# btkb.net
KiCad netlist of a schematic drawn in EAGLE
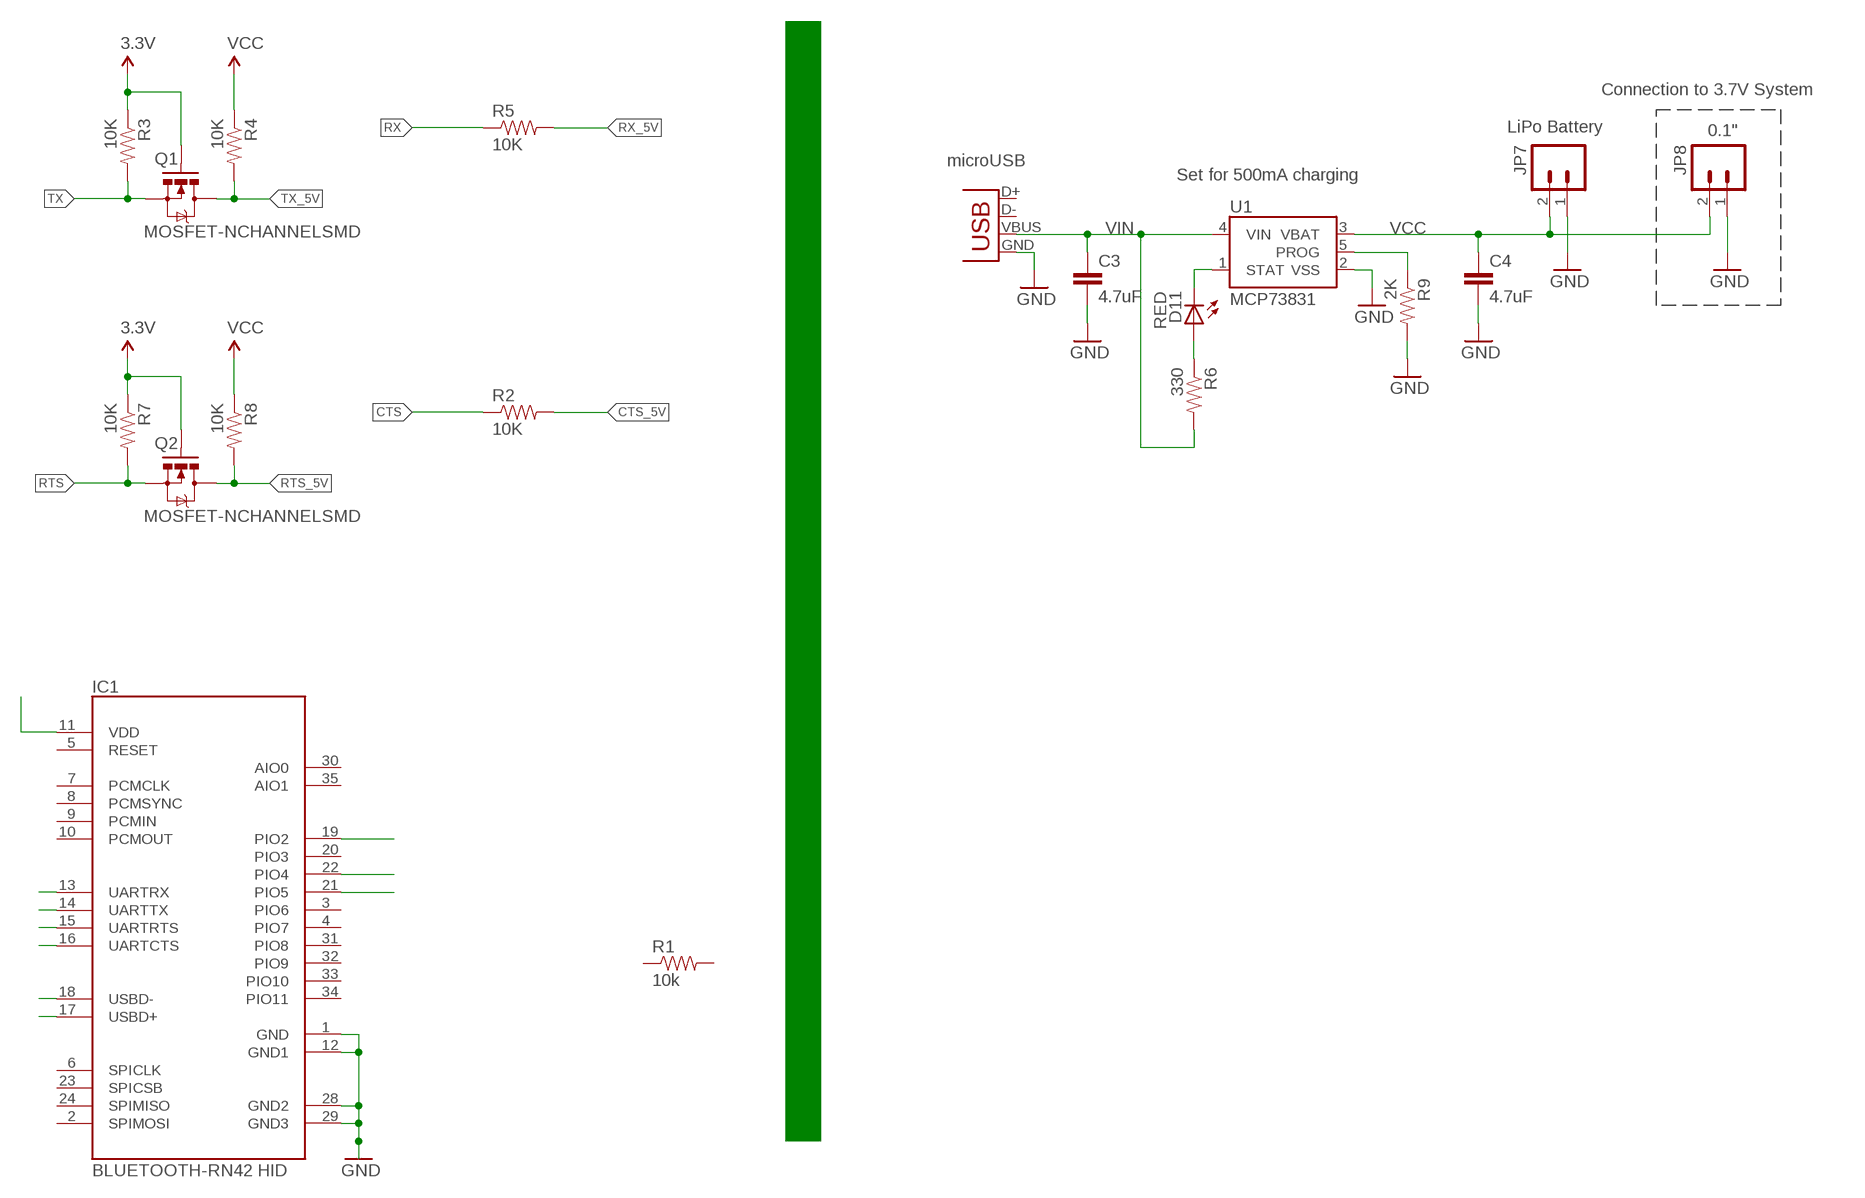
[diagram p0: schematic, sheet 1]

(export (version "E")
  (design (tool "Eeschema 10.0.6"))
  (components
    (comp (ref "C3")
      (value "4.7uF")
      (footprint "eagle-import:0402-CAP")
      (libsource (lib "eagle-import") (part "CAP0402-CAP"))
    )
    (comp (ref "C4")
      (value "4.7uF")
      (footprint "eagle-import:0402-CAP")
      (libsource (lib "eagle-import") (part "CAP0402-CAP"))
    )
    (comp (ref "D11")
      (value "RED")
      (footprint "eagle-import:LED-0603")
      (libsource (lib "eagle-import") (part "LED0603"))
    )
    (comp (ref "IC1")
      (value "BLUETOOTH-RN42 HID")
      (footprint "eagle-import:RN41")
      (libsource (lib "eagle-import") (part "BLUETOOTH-RN41{dblquote}"))
    )
    (comp (ref "JP7")
      (value "LiPo Battery")
      (footprint "eagle-import:JST-2-SMD")
      (libsource (lib "eagle-import") (part "M02-JST-2MM-SMT"))
    )
    (comp (ref "JP8")
      (value "M02PTH")
      (footprint "eagle-import:1X02")
      (libsource (lib "eagle-import") (part "M02PTH"))
    )
    (comp (ref "Q1")
      (value "MOSFET-NCHANNELSMD")
      (footprint "eagle-import:SOT23-3")
      (libsource (lib "eagle-import") (part "MOSFET-NCHANNELSMD"))
    )
    (comp (ref "Q2")
      (value "MOSFET-NCHANNELSMD")
      (footprint "eagle-import:SOT23-3")
      (libsource (lib "eagle-import") (part "MOSFET-NCHANNELSMD"))
    )
    (comp (ref "R1")
      (value "10k")
      (footprint "eagle-import:0805")
      (libsource (lib "eagle-import") (part "0.22OHM-1/4W-1%(0805)"))
    )
    (comp (ref "R2")
      (value "10K")
      (footprint "eagle-import:0603-RES")
      (libsource (lib "eagle-import") (part "RESISTOR0603-RES"))
    )
    (comp (ref "R3")
      (value "10K")
      (footprint "eagle-import:0603-RES")
      (libsource (lib "eagle-import") (part "RESISTOR0603-RES"))
    )
    (comp (ref "R4")
      (value "10K")
      (footprint "eagle-import:0603-RES")
      (libsource (lib "eagle-import") (part "RESISTOR0603-RES"))
    )
    (comp (ref "R5")
      (value "10K")
      (footprint "eagle-import:0603-RES")
      (libsource (lib "eagle-import") (part "RESISTOR0603-RES"))
    )
    (comp (ref "R6")
      (value "330")
      (footprint "eagle-import:0402-RES")
      (libsource (lib "eagle-import") (part "RESISTOR0402-RES"))
    )
    (comp (ref "R7")
      (value "10K")
      (footprint "eagle-import:0603-RES")
      (libsource (lib "eagle-import") (part "RESISTOR0603-RES"))
    )
    (comp (ref "R8")
      (value "10K")
      (footprint "eagle-import:0603-RES")
      (libsource (lib "eagle-import") (part "RESISTOR0603-RES"))
    )
    (comp (ref "R9")
      (value "2K")
      (footprint "eagle-import:0402-RES")
      (libsource (lib "eagle-import") (part "RESISTOR0402-RES"))
    )
    (comp (ref "U1")
      (value "MCP73831")
      (footprint "eagle-import:SOT23-5")
      (libsource (lib "eagle-import") (part "MCP73831"))
    )
    (comp (ref "X1")
      (value "Micro USB")
      (footprint "eagle-import:USB-MICROB")
      (libsource (lib "eagle-import") (part "USB-MICROB"))
    )
  )
  (nets
    (net (code "1") (name "/VIN") (class "Default")
      (node (ref "C3") (pin "1") (pinfunction "1_1") (pintype "passive"))
      (node (ref "R6") (pin "2") (pinfunction "2_2") (pintype "passive"))
      (node (ref "U1") (pin "4") (pinfunction "VIN_4") (pintype "power_in"))
      (node (ref "X1") (pin "VBUS") (pinfunction "VBUS_VBUS") (pintype "bidirectional"))
    )
    (net (code "2") (name "3.3V") (class "Default")
      (node (ref "Q1") (pin "1") (pinfunction "G_1") (pintype "passive"))
      (node (ref "Q2") (pin "1") (pinfunction "G_1") (pintype "passive"))
      (node (ref "R3") (pin "1") (pinfunction "1_1") (pintype "passive"))
      (node (ref "R7") (pin "1") (pinfunction "1_1") (pintype "passive"))
    )
    (net (code "3") (name "CTS") (class "Default")
      (node (ref "R2") (pin "1") (pinfunction "1_1") (pintype "passive"))
    )
    (net (code "4") (name "CTS_5V") (class "Default")
      (node (ref "R2") (pin "2") (pinfunction "2_2") (pintype "passive"))
    )
    (net (code "5") (name "GND") (class "Default")
      (node (ref "C3") (pin "2") (pinfunction "2_2") (pintype "passive"))
      (node (ref "C4") (pin "2") (pinfunction "2_2") (pintype "passive"))
      (node (ref "IC1") (pin "1") (pinfunction "GND_1") (pintype "bidirectional"))
      (node (ref "IC1") (pin "12") (pinfunction "GND1_12") (pintype "bidirectional"))
      (node (ref "IC1") (pin "28") (pinfunction "GND2_28") (pintype "bidirectional"))
      (node (ref "IC1") (pin "29") (pinfunction "GND3_29") (pintype "bidirectional"))
      (node (ref "JP7") (pin "1") (pinfunction "1_1") (pintype "passive"))
      (node (ref "JP8") (pin "1") (pinfunction "1_1") (pintype "passive"))
      (node (ref "R9") (pin "2") (pinfunction "2_2") (pintype "passive"))
      (node (ref "U1") (pin "2") (pinfunction "VSS_2") (pintype "power_in"))
      (node (ref "X1") (pin "GND") (pinfunction "GND_GND") (pintype "bidirectional"))
    )
    (net (code "6") (name "Net-(D11-PadA)") (class "Default")
      (node (ref "D11") (pin "A") (pinfunction "A_A") (pintype "passive"))
      (node (ref "R6") (pin "1") (pinfunction "1_1") (pintype "passive"))
    )
    (net (code "7") (name "Net-(U1-PROG)") (class "Default")
      (node (ref "R9") (pin "1") (pinfunction "1_1") (pintype "passive"))
      (node (ref "U1") (pin "5") (pinfunction "PROG_5") (pintype "input"))
    )
    (net (code "8") (name "Net-(U1-STAT)") (class "Default")
      (node (ref "D11") (pin "C") (pinfunction "C_C") (pintype "passive"))
      (node (ref "U1") (pin "1") (pinfunction "STAT_1") (pintype "output"))
    )
    (net (code "9") (name "RTS") (class "Default")
      (node (ref "Q2") (pin "2") (pinfunction "S_2") (pintype "passive"))
      (node (ref "R7") (pin "2") (pinfunction "2_2") (pintype "passive"))
    )
    (net (code "10") (name "RTS_5V") (class "Default")
      (node (ref "Q2") (pin "3") (pinfunction "D_3") (pintype "passive"))
      (node (ref "R8") (pin "2") (pinfunction "2_2") (pintype "passive"))
    )
    (net (code "11") (name "RX") (class "Default")
      (node (ref "R5") (pin "1") (pinfunction "1_1") (pintype "passive"))
    )
    (net (code "12") (name "RX_5V") (class "Default")
      (node (ref "R5") (pin "2") (pinfunction "2_2") (pintype "passive"))
    )
    (net (code "13") (name "TX") (class "Default")
      (node (ref "Q1") (pin "2") (pinfunction "S_2") (pintype "passive"))
      (node (ref "R3") (pin "2") (pinfunction "2_2") (pintype "passive"))
    )
    (net (code "14") (name "TX_5V") (class "Default")
      (node (ref "Q1") (pin "3") (pinfunction "D_3") (pintype "passive"))
      (node (ref "R4") (pin "2") (pinfunction "2_2") (pintype "passive"))
    )
    (net (code "15") (name "VCC") (class "Default")
      (node (ref "C4") (pin "1") (pinfunction "1_1") (pintype "passive"))
      (node (ref "JP7") (pin "2") (pinfunction "2_2") (pintype "passive"))
      (node (ref "JP8") (pin "2") (pinfunction "2_2") (pintype "passive"))
      (node (ref "R4") (pin "1") (pinfunction "1_1") (pintype "passive"))
      (node (ref "R8") (pin "1") (pinfunction "1_1") (pintype "passive"))
      (node (ref "U1") (pin "3") (pinfunction "VBAT_3") (pintype "power_in"))
    )
    (net (code "16") (name "unconnected-(IC1-AIO0-Pad30)") (class "Default")
      (node (ref "IC1") (pin "30") (pinfunction "AIO0_30") (pintype "bidirectional"))
    )
    (net (code "17") (name "unconnected-(IC1-AIO1-Pad35)") (class "Default")
      (node (ref "IC1") (pin "35") (pinfunction "AIO1_35") (pintype "bidirectional"))
    )
    (net (code "18") (name "unconnected-(IC1-PCMCLK-Pad7)") (class "Default")
      (node (ref "IC1") (pin "7") (pinfunction "PCMCLK_7") (pintype "bidirectional"))
    )
    (net (code "19") (name "unconnected-(IC1-PCMIN-Pad9)") (class "Default")
      (node (ref "IC1") (pin "9") (pinfunction "PCMIN_9") (pintype "bidirectional"))
    )
    (net (code "20") (name "unconnected-(IC1-PCMOUT-Pad10)") (class "Default")
      (node (ref "IC1") (pin "10") (pinfunction "PCMOUT_10") (pintype "bidirectional"))
    )
    (net (code "21") (name "unconnected-(IC1-PCMSYNC-Pad8)") (class "Default")
      (node (ref "IC1") (pin "8") (pinfunction "PCMSYNC_8") (pintype "bidirectional"))
    )
    (net (code "22") (name "unconnected-(IC1-PIO2-Pad19)") (class "Default")
      (node (ref "IC1") (pin "19") (pinfunction "PIO2_19") (pintype "bidirectional"))
    )
    (net (code "23") (name "unconnected-(IC1-PIO3-Pad20)") (class "Default")
      (node (ref "IC1") (pin "20") (pinfunction "PIO3_20") (pintype "bidirectional"))
    )
    (net (code "24") (name "unconnected-(IC1-PIO4-Pad22)") (class "Default")
      (node (ref "IC1") (pin "22") (pinfunction "PIO4_22") (pintype "bidirectional"))
    )
    (net (code "25") (name "unconnected-(IC1-PIO5-Pad21)") (class "Default")
      (node (ref "IC1") (pin "21") (pinfunction "PIO5_21") (pintype "bidirectional"))
    )
    (net (code "26") (name "unconnected-(IC1-PIO6-Pad3)") (class "Default")
      (node (ref "IC1") (pin "3") (pinfunction "PIO6_3") (pintype "bidirectional"))
    )
    (net (code "27") (name "unconnected-(IC1-PIO7-Pad4)") (class "Default")
      (node (ref "IC1") (pin "4") (pinfunction "PIO7_4") (pintype "bidirectional"))
    )
    (net (code "28") (name "unconnected-(IC1-PIO8-Pad31)") (class "Default")
      (node (ref "IC1") (pin "31") (pinfunction "PIO8_31") (pintype "bidirectional"))
    )
    (net (code "29") (name "unconnected-(IC1-PIO9-Pad32)") (class "Default")
      (node (ref "IC1") (pin "32") (pinfunction "PIO9_32") (pintype "bidirectional"))
    )
    (net (code "30") (name "unconnected-(IC1-PIO10-Pad33)") (class "Default")
      (node (ref "IC1") (pin "33") (pinfunction "PIO10_33") (pintype "bidirectional"))
    )
    (net (code "31") (name "unconnected-(IC1-PIO11-Pad34)") (class "Default")
      (node (ref "IC1") (pin "34") (pinfunction "PIO11_34") (pintype "bidirectional"))
    )
    (net (code "32") (name "unconnected-(IC1-RESET-Pad5)") (class "Default")
      (node (ref "IC1") (pin "5") (pinfunction "RESET_5") (pintype "bidirectional"))
    )
    (net (code "33") (name "unconnected-(IC1-SPICLK-Pad6)") (class "Default")
      (node (ref "IC1") (pin "6") (pinfunction "SPICLK_6") (pintype "bidirectional"))
    )
    (net (code "34") (name "unconnected-(IC1-SPICSB-Pad23)") (class "Default")
      (node (ref "IC1") (pin "23") (pinfunction "SPICSB_23") (pintype "bidirectional"))
    )
    (net (code "35") (name "unconnected-(IC1-SPIMISO-Pad24)") (class "Default")
      (node (ref "IC1") (pin "24") (pinfunction "SPIMISO_24") (pintype "bidirectional"))
    )
    (net (code "36") (name "unconnected-(IC1-SPIMOSI-Pad2)") (class "Default")
      (node (ref "IC1") (pin "2") (pinfunction "SPIMOSI_2") (pintype "bidirectional"))
    )
    (net (code "37") (name "unconnected-(IC1-UARTCTS-Pad16)") (class "Default")
      (node (ref "IC1") (pin "16") (pinfunction "UARTCTS_16") (pintype "bidirectional"))
    )
    (net (code "38") (name "unconnected-(IC1-UARTRTS-Pad15)") (class "Default")
      (node (ref "IC1") (pin "15") (pinfunction "UARTRTS_15") (pintype "bidirectional"))
    )
    (net (code "39") (name "unconnected-(IC1-UARTRX-Pad13)") (class "Default")
      (node (ref "IC1") (pin "13") (pinfunction "UARTRX_13") (pintype "bidirectional"))
    )
    (net (code "40") (name "unconnected-(IC1-UARTTX-Pad14)") (class "Default")
      (node (ref "IC1") (pin "14") (pinfunction "UARTTX_14") (pintype "bidirectional"))
    )
    (net (code "41") (name "unconnected-(IC1-USBD+-Pad17)") (class "Default")
      (node (ref "IC1") (pin "17") (pinfunction "USBD+_17") (pintype "bidirectional"))
    )
    (net (code "42") (name "unconnected-(IC1-USBD--Pad18)") (class "Default")
      (node (ref "IC1") (pin "18") (pinfunction "USBD-_18") (pintype "bidirectional"))
    )
    (net (code "43") (name "unconnected-(IC1-VDD-Pad11)") (class "Default")
      (node (ref "IC1") (pin "11") (pinfunction "VDD_11") (pintype "bidirectional"))
    )
    (net (code "44") (name "unconnected-(R1-Pad1)") (class "Default")
      (node (ref "R1") (pin "1") (pinfunction "1_1") (pintype "passive"))
    )
    (net (code "45") (name "unconnected-(R1-Pad2)") (class "Default")
      (node (ref "R1") (pin "2") (pinfunction "2_2") (pintype "passive"))
    )
    (net (code "46") (name "unconnected-(X1-PadD+)") (class "Default")
      (node (ref "X1") (pin "D+") (pinfunction "D+_D+") (pintype "bidirectional"))
    )
    (net (code "47") (name "unconnected-(X1-PadD-)") (class "Default")
      (node (ref "X1") (pin "D-") (pinfunction "D-_D-") (pintype "bidirectional"))
    )
  )
)
